# POWER.net
KiCad netlist of a schematic drawn in Altium Designer
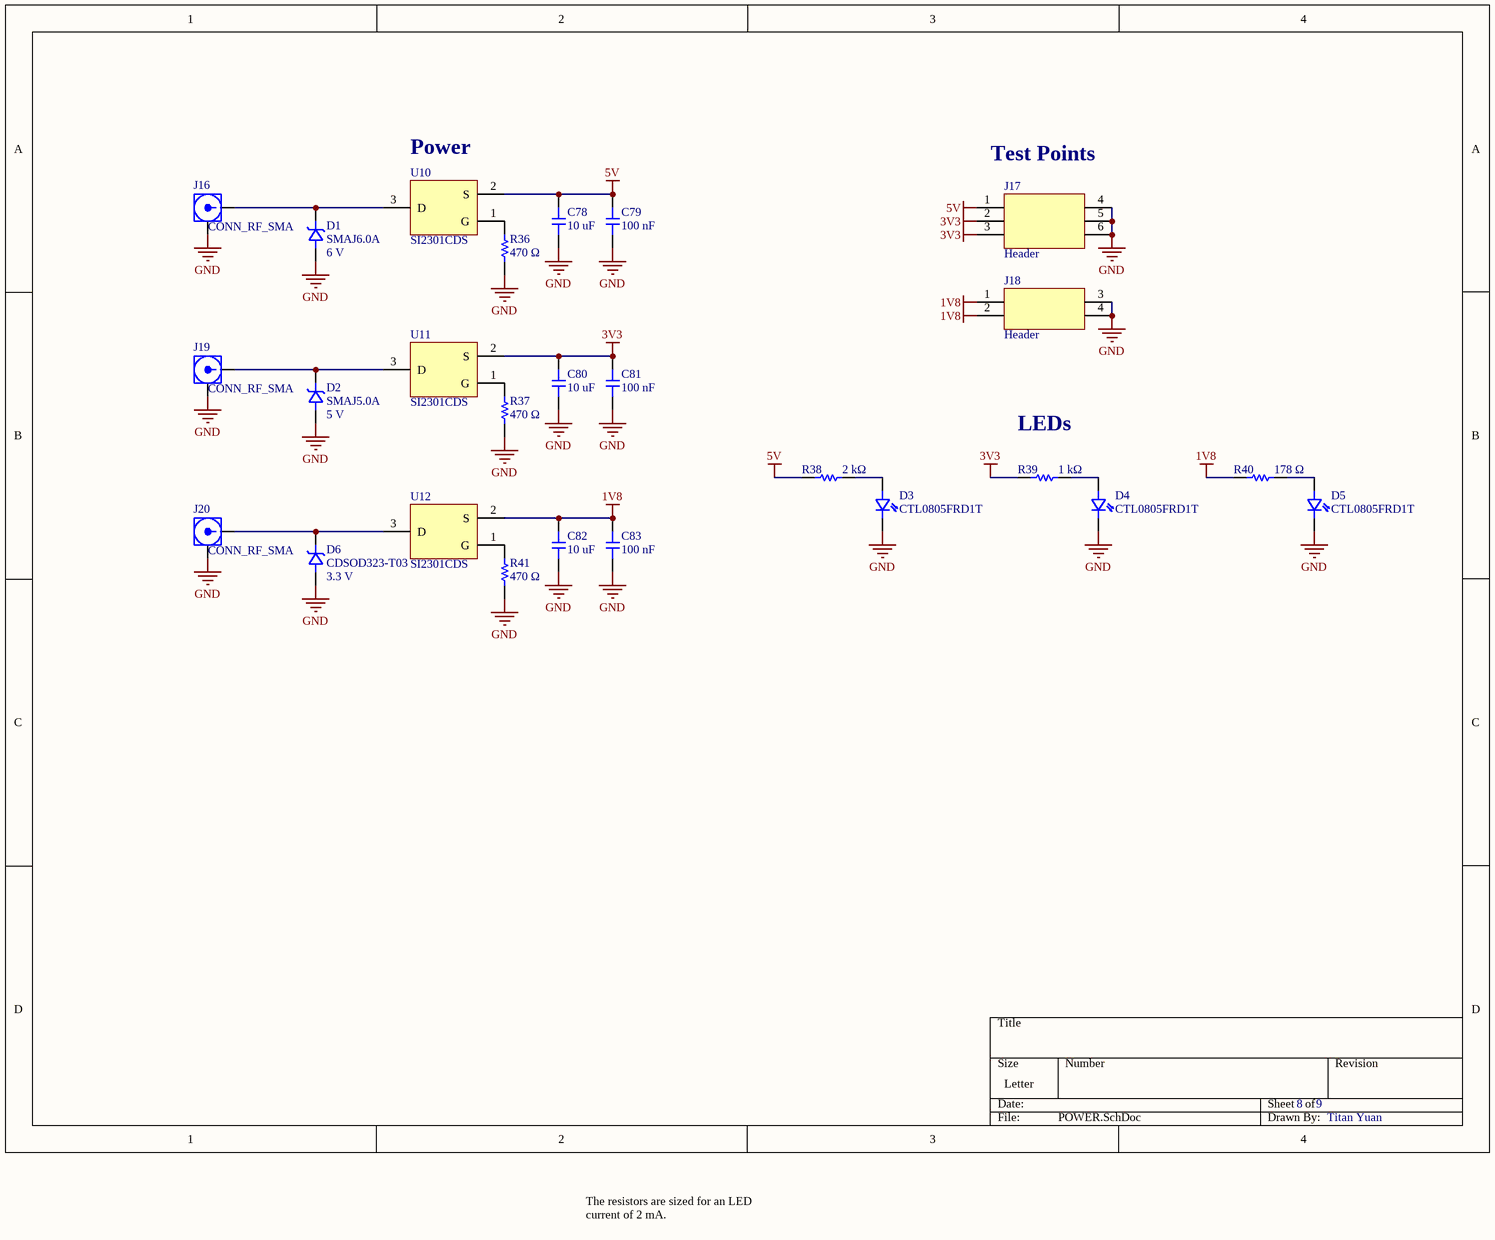
[diagram p0: POWER.SchDoc]

(export (version "E")
  (design (tool "Eeschema 10.0.6"))
  (components
    (comp (ref "C78")
      (value "10 uF")
      (footprint "CAP_0603")
      (description "10V 10uF X7R ±10% 0603 Multilayer Ceramic Capacitors MLCC - SMD/SMT ROHS")
      (fields
        (field (name "MANUFACTURER") "Murata Electronics")
        (field (name "MANUFACTURER PART NUMBER") "GRM188Z71A106KA73D")
      )
      (libsource (lib "Titan") (part "CAP"))
    )
    (comp (ref "C79")
      (value "100 nF")
      (footprint "CAP_0402")
      (description "Ceramic Capacitor, Ceramic, 50V, 10% +Tol, 10% -Tol, X7R, 15% TC, 0.1uF, Surface Mount, 0402")
      (fields
        (field (name "MANUFACTURER") "Yageo")
        (field (name "MANUFACTURER PART NUMBER") "CC0402KPX7R9BB104")
      )
      (libsource (lib "Titan") (part "CAP"))
    )
    (comp (ref "C80")
      (value "10 uF")
      (footprint "CAP_0603")
      (description "10V 10uF X7R ±10% 0603 Multilayer Ceramic Capacitors MLCC - SMD/SMT ROHS")
      (fields
        (field (name "MANUFACTURER") "Murata Electronics")
        (field (name "MANUFACTURER PART NUMBER") "GRM188Z71A106KA73D")
      )
      (libsource (lib "Titan") (part "CAP"))
    )
    (comp (ref "C81")
      (value "100 nF")
      (footprint "CAP_0402")
      (description "Ceramic Capacitor, Ceramic, 50V, 10% +Tol, 10% -Tol, X7R, 15% TC, 0.1uF, Surface Mount, 0402")
      (fields
        (field (name "MANUFACTURER") "Yageo")
        (field (name "MANUFACTURER PART NUMBER") "CC0402KPX7R9BB104")
      )
      (libsource (lib "Titan") (part "CAP"))
    )
    (comp (ref "C82")
      (value "10 uF")
      (footprint "CAP_0603")
      (description "10V 10uF X7R ±10% 0603 Multilayer Ceramic Capacitors MLCC - SMD/SMT ROHS")
      (fields
        (field (name "MANUFACTURER") "Murata Electronics")
        (field (name "MANUFACTURER PART NUMBER") "GRM188Z71A106KA73D")
      )
      (libsource (lib "Titan") (part "CAP"))
    )
    (comp (ref "C83")
      (value "100 nF")
      (footprint "CAP_0402")
      (description "Ceramic Capacitor, Ceramic, 50V, 10% +Tol, 10% -Tol, X7R, 15% TC, 0.1uF, Surface Mount, 0402")
      (fields
        (field (name "MANUFACTURER") "Yageo")
        (field (name "MANUFACTURER PART NUMBER") "CC0402KPX7R9BB104")
      )
      (libsource (lib "Titan") (part "CAP"))
    )
    (comp (ref "D1")
      (value "SMAJ6.0A")
      (footprint "SMAJ")
      (description "SMAJ Series 10.3 V 0.4 kW Surface Mount Uni-Directional TVS Diode - DO-214AC")
      (fields
        (field (name "MANUFACTURER") "Littelfuse Inc.")
        (field (name "REVERSE STANDOFF VOLTAGE") "6 V")
        (field (name "VOLTAGE") "60V")
      )
      (libsource (lib "Titan") (part "SMAJ6.0A"))
    )
    (comp (ref "D2")
      (value "SMAJ5.0A")
      (footprint "SMAJ")
      (description "SMAJ Series 9.2 V 400 W Surface Mount Uni-Directional TVS Diode - DO-214AC")
      (fields (field (name "MANUFACTURER") "Littelfuse Inc.") (field (name "REVERSE STANDOFF VOLTAGE") "5 V"))
      (libsource (lib "Titan") (part "SMAJ5.0A"))
    )
    (comp (ref "D3")
      (value "CTL0805FRD1T")
      (footprint "CTL0805FRD1T")
      (description "Chip Type LED, 0805, Flat Lens, Red")
      (fields
        (field (name "MANUFACTURER") "Venkel")
        (field (name "MANUFACTURER PART NUMBER") "CTL0805FRD1T-CT")
      )
      (libsource (lib "Titan") (part "CTL0805FRD1T"))
    )
    (comp (ref "D4")
      (value "CTL0805FRD1T")
      (footprint "CTL0805FRD1T")
      (description "Chip Type LED, 0805, Flat Lens, Red")
      (fields
        (field (name "MANUFACTURER") "Venkel")
        (field (name "MANUFACTURER PART NUMBER") "CTL0805FRD1T-CT")
      )
      (libsource (lib "Titan") (part "CTL0805FRD1T"))
    )
    (comp (ref "D5")
      (value "CTL0805FRD1T")
      (footprint "CTL0805FRD1T")
      (description "Chip Type LED, 0805, Flat Lens, Red")
      (fields
        (field (name "MANUFACTURER") "Venkel")
        (field (name "MANUFACTURER PART NUMBER") "CTL0805FRD1T-CT")
      )
      (libsource (lib "Titan") (part "CTL0805FRD1T"))
    )
    (comp (ref "D6")
      (value "CDSOD323-T03")
      (footprint "CDSOD323")
      (description "ESD protection diodes / TVS diodes; BOURNS; CDSOD323-T03; 19 V; 20 A; 3.3 V; 4 V")
      (fields (field (name "MANUFACTURER") "Bourns Inc.") (field (name "REVERSE STANDOFF VOLTAGE") "3.3 V"))
      (libsource (lib "Titan") (part "CDSOD323-T03"))
    )
    (comp (ref "J16")
      (value "CONN_RF_SMA")
      (footprint "142-0701-801")
      (description "RF / Coaxial Connector, SMA Coaxial, Straight Jack, Solder, 50 ohm, Beryllium Copper")
      (fields
        (field (name "MANUFACTURER") "Cinch Connectivity Solutions Johnson")
        (field (name "MANUFACTURER PART NUMBER") "142-0701-801")
      )
      (libsource (lib "Titan") (part "CONN_RF_SMA"))
    )
    (comp (ref "J17")
      (value "Header")
      (footprint "CONN_2x3_2.54mm_PinHeader_Vertical")
      (description "Pin Header, Board-to-Board, 2.54 mm, 2 Rows, 6 Contacts, Through Hole, TSW Series")
      (fields
        (field (name "MANUFACTURER") "Samtec")
        (field (name "MANUFACTURER PART NUMBER") "TSW-103-07-F-D")
      )
      (libsource (lib "Titan") (part "CONN_2x3_2.54mm_PinHeader_Vertical"))
    )
    (comp (ref "J18")
      (value "Header")
      (footprint "CONN_2x2_2.54mm_PinHeader_Vertical")
      (description "Pin Header, Board-to-Board, 2.54 mm, 2 Rows, 4 Contacts, Through Hole, TSW Series")
      (fields
        (field (name "MANUFACTURER") "Samtec")
        (field (name "MANUFACTURER PART NUMBER") "TSW-102-07-F-D")
      )
      (libsource (lib "Titan") (part "CONN_2x2_2.54mm_PinHeader_Vertical"))
    )
    (comp (ref "J19")
      (value "CONN_RF_SMA")
      (footprint "142-0701-801")
      (description "RF / Coaxial Connector, SMA Coaxial, Straight Jack, Solder, 50 ohm, Beryllium Copper")
      (fields
        (field (name "MANUFACTURER") "Cinch Connectivity Solutions Johnson")
        (field (name "MANUFACTURER PART NUMBER") "142-0701-801")
      )
      (libsource (lib "Titan") (part "CONN_RF_SMA"))
    )
    (comp (ref "J20")
      (value "CONN_RF_SMA")
      (footprint "142-0701-801")
      (description "RF / Coaxial Connector, SMA Coaxial, Straight Jack, Solder, 50 ohm, Beryllium Copper")
      (fields
        (field (name "MANUFACTURER") "Cinch Connectivity Solutions Johnson")
        (field (name "MANUFACTURER PART NUMBER") "142-0701-801")
      )
      (libsource (lib "Titan") (part "CONN_RF_SMA"))
    )
    (comp (ref "R36")
      (value "470 Ω")
      (footprint "RES_0402")
      (description "Res Thick Film 0402 470 Ohm 1% 0.063W(1/16W) ±100ppm/C Pad SMD T/R")
      (fields
        (field (name "MANUFACTURER") "Yageo")
        (field (name "MANUFACTURER PART NUMBER") "RC0402FR-07470RL")
      )
      (libsource (lib "Titan") (part "RES"))
    )
    (comp (ref "R37")
      (value "470 Ω")
      (footprint "RES_0402")
      (description "Res Thick Film 0402 470 Ohm 1% 0.063W(1/16W) ±100ppm/C Pad SMD T/R")
      (fields
        (field (name "MANUFACTURER") "Yageo")
        (field (name "MANUFACTURER PART NUMBER") "RC0402FR-07470RL")
      )
      (libsource (lib "Titan") (part "RES"))
    )
    (comp (ref "R38")
      (value "2 kΩ")
      (footprint "RES_0603")
      (description "100Mw Thick Film Resistors 100Ppm/ 1% 2K 0603 Chip Resistor Surface Mount Rohs")
      (fields
        (field (name "MANUFACTURER") "Yageo")
        (field (name "MANUFACTURER PART NUMBER") "RC0603FR-072KL")
      )
      (libsource (lib "Titan") (part "RES"))
    )
    (comp (ref "R39")
      (value "1 kΩ")
      (footprint "RES_0603")
      (description "100mW Thick Film Resistors 75V ±100ppm/℃ ±1% 1kΩ 0603 Chip Resistor - Surface Mount ROHS")
      (fields
        (field (name "MANUFACTURER") "Yageo")
        (field (name "MANUFACTURER PART NUMBER") "RC0603FR-071KL")
      )
      (libsource (lib "Titan") (part "RES"))
    )
    (comp (ref "R40")
      (value "178 Ω")
      (footprint "RES_0603")
      (description "Res Thick Film 0603 178 Ohm 1% 0.1W(1/10W) ±100ppm/C Pad SMD T/R")
      (fields
        (field (name "MANUFACTURER") "Yageo")
        (field (name "MANUFACTURER PART NUMBER") "RC0603FR-07178RL")
      )
      (libsource (lib "Titan") (part "RES"))
    )
    (comp (ref "R41")
      (value "470 Ω")
      (footprint "RES_0402")
      (description "Res Thick Film 0402 470 Ohm 1% 0.063W(1/16W) ±100ppm/C Pad SMD T/R")
      (fields
        (field (name "MANUFACTURER") "Yageo")
        (field (name "MANUFACTURER PART NUMBER") "RC0402FR-07470RL")
      )
      (libsource (lib "Titan") (part "RES"))
    )
    (comp (ref "U10")
      (value "SI2301CDS")
      (footprint "SI2301CDS")
      (description "P-ch Mosfet SOT-23 20V 112MOHM @ 4.5V - Lead(pb) And Halogen Free")
      (fields
        (field (name "MANUFACTURER") "Vishay Siliconix")
        (field (name "MANUFACTURER PART NUMBER") "SI2301CDS-T1-GE3")
      )
      (libsource (lib "Titan") (part "SI2301CDS"))
    )
    (comp (ref "U11")
      (value "SI2301CDS")
      (footprint "SI2301CDS")
      (description "P-ch Mosfet SOT-23 20V 112MOHM @ 4.5V - Lead(pb) And Halogen Free")
      (fields
        (field (name "MANUFACTURER") "Vishay Siliconix")
        (field (name "MANUFACTURER PART NUMBER") "SI2301CDS-T1-GE3")
      )
      (libsource (lib "Titan") (part "SI2301CDS"))
    )
    (comp (ref "U12")
      (value "SI2301CDS")
      (footprint "SI2301CDS")
      (description "P-ch Mosfet SOT-23 20V 112MOHM @ 4.5V - Lead(pb) And Halogen Free")
      (fields
        (field (name "MANUFACTURER") "Vishay Siliconix")
        (field (name "MANUFACTURER PART NUMBER") "SI2301CDS-T1-GE3")
      )
      (libsource (lib "Titan") (part "SI2301CDS"))
    )
  )
  (nets
    (net (code "1") (name "1V8") (class "Default")
      (node (ref "C82") (pin "2") (pintype "passive"))
      (node (ref "C83") (pin "2") (pintype "passive"))
      (node (ref "J18") (pin "1") (pintype "passive"))
      (node (ref "J18") (pin "2") (pintype "passive"))
      (node (ref "R40") (pin "1") (pintype "passive"))
      (node (ref "U12") (pin "2") (pinfunction "S_2") (pintype "passive"))
    )
    (net (code "2") (name "3V3") (class "Default")
      (node (ref "C80") (pin "2") (pintype "passive"))
      (node (ref "C81") (pin "2") (pintype "passive"))
      (node (ref "J17") (pin "2") (pintype "passive"))
      (node (ref "J17") (pin "3") (pintype "passive"))
      (node (ref "R39") (pin "1") (pintype "passive"))
      (node (ref "U11") (pin "2") (pinfunction "S_2") (pintype "passive"))
    )
    (net (code "3") (name "5V") (class "Default")
      (node (ref "C78") (pin "2") (pintype "passive"))
      (node (ref "C79") (pin "2") (pintype "passive"))
      (node (ref "J17") (pin "1") (pintype "passive"))
      (node (ref "R38") (pin "1") (pintype "passive"))
      (node (ref "U10") (pin "2") (pinfunction "S_2") (pintype "passive"))
    )
    (net (code "4") (name "GND") (class "Default")
      (node (ref "C78") (pin "1") (pintype "passive"))
      (node (ref "C79") (pin "1") (pintype "passive"))
      (node (ref "C80") (pin "1") (pintype "passive"))
      (node (ref "C81") (pin "1") (pintype "passive"))
      (node (ref "C82") (pin "1") (pintype "passive"))
      (node (ref "C83") (pin "1") (pintype "passive"))
      (node (ref "D1") (pin "2") (pintype "passive"))
      (node (ref "D2") (pin "2") (pintype "passive"))
      (node (ref "D3") (pin "1") (pintype "passive"))
      (node (ref "D4") (pin "1") (pintype "passive"))
      (node (ref "D5") (pin "1") (pintype "passive"))
      (node (ref "D6") (pin "2") (pintype "passive"))
      (node (ref "J16") (pin "2") (pintype "passive"))
      (node (ref "J17") (pin "4") (pintype "passive"))
      (node (ref "J17") (pin "5") (pintype "passive"))
      (node (ref "J17") (pin "6") (pintype "passive"))
      (node (ref "J18") (pin "3") (pintype "passive"))
      (node (ref "J18") (pin "4") (pintype "passive"))
      (node (ref "J19") (pin "2") (pintype "passive"))
      (node (ref "J20") (pin "2") (pintype "passive"))
      (node (ref "R36") (pin "1") (pintype "passive"))
      (node (ref "R37") (pin "1") (pintype "passive"))
      (node (ref "R41") (pin "1") (pintype "passive"))
    )
    (net (code "5") (name "Net-(D3-Pad2)") (class "Default")
      (node (ref "D3") (pin "2") (pintype "passive"))
      (node (ref "R38") (pin "2") (pintype "passive"))
    )
    (net (code "6") (name "Net-(D4-Pad2)") (class "Default")
      (node (ref "D4") (pin "2") (pintype "passive"))
      (node (ref "R39") (pin "2") (pintype "passive"))
    )
    (net (code "7") (name "Net-(D5-Pad2)") (class "Default")
      (node (ref "D5") (pin "2") (pintype "passive"))
      (node (ref "R40") (pin "2") (pintype "passive"))
    )
    (net (code "8") (name "Net-(U10-D)") (class "Default")
      (node (ref "D1") (pin "1") (pintype "passive"))
      (node (ref "J16") (pin "1") (pintype "passive"))
      (node (ref "U10") (pin "3") (pinfunction "D_3") (pintype "passive"))
    )
    (net (code "9") (name "Net-(U10-G)") (class "Default")
      (node (ref "R36") (pin "2") (pintype "passive"))
      (node (ref "U10") (pin "1") (pinfunction "G_1") (pintype "passive"))
    )
    (net (code "10") (name "Net-(U11-D)") (class "Default")
      (node (ref "D2") (pin "1") (pintype "passive"))
      (node (ref "J19") (pin "1") (pintype "passive"))
      (node (ref "U11") (pin "3") (pinfunction "D_3") (pintype "passive"))
    )
    (net (code "11") (name "Net-(U11-G)") (class "Default")
      (node (ref "R37") (pin "2") (pintype "passive"))
      (node (ref "U11") (pin "1") (pinfunction "G_1") (pintype "passive"))
    )
    (net (code "12") (name "Net-(U12-D)") (class "Default")
      (node (ref "D6") (pin "1") (pintype "passive"))
      (node (ref "J20") (pin "1") (pintype "passive"))
      (node (ref "U12") (pin "3") (pinfunction "D_3") (pintype "passive"))
    )
    (net (code "13") (name "Net-(U12-G)") (class "Default")
      (node (ref "R41") (pin "2") (pintype "passive"))
      (node (ref "U12") (pin "1") (pinfunction "G_1") (pintype "passive"))
    )
  )
)
